# LED-Globe.net
KiCad netlist of a schematic drawn in EAGLE
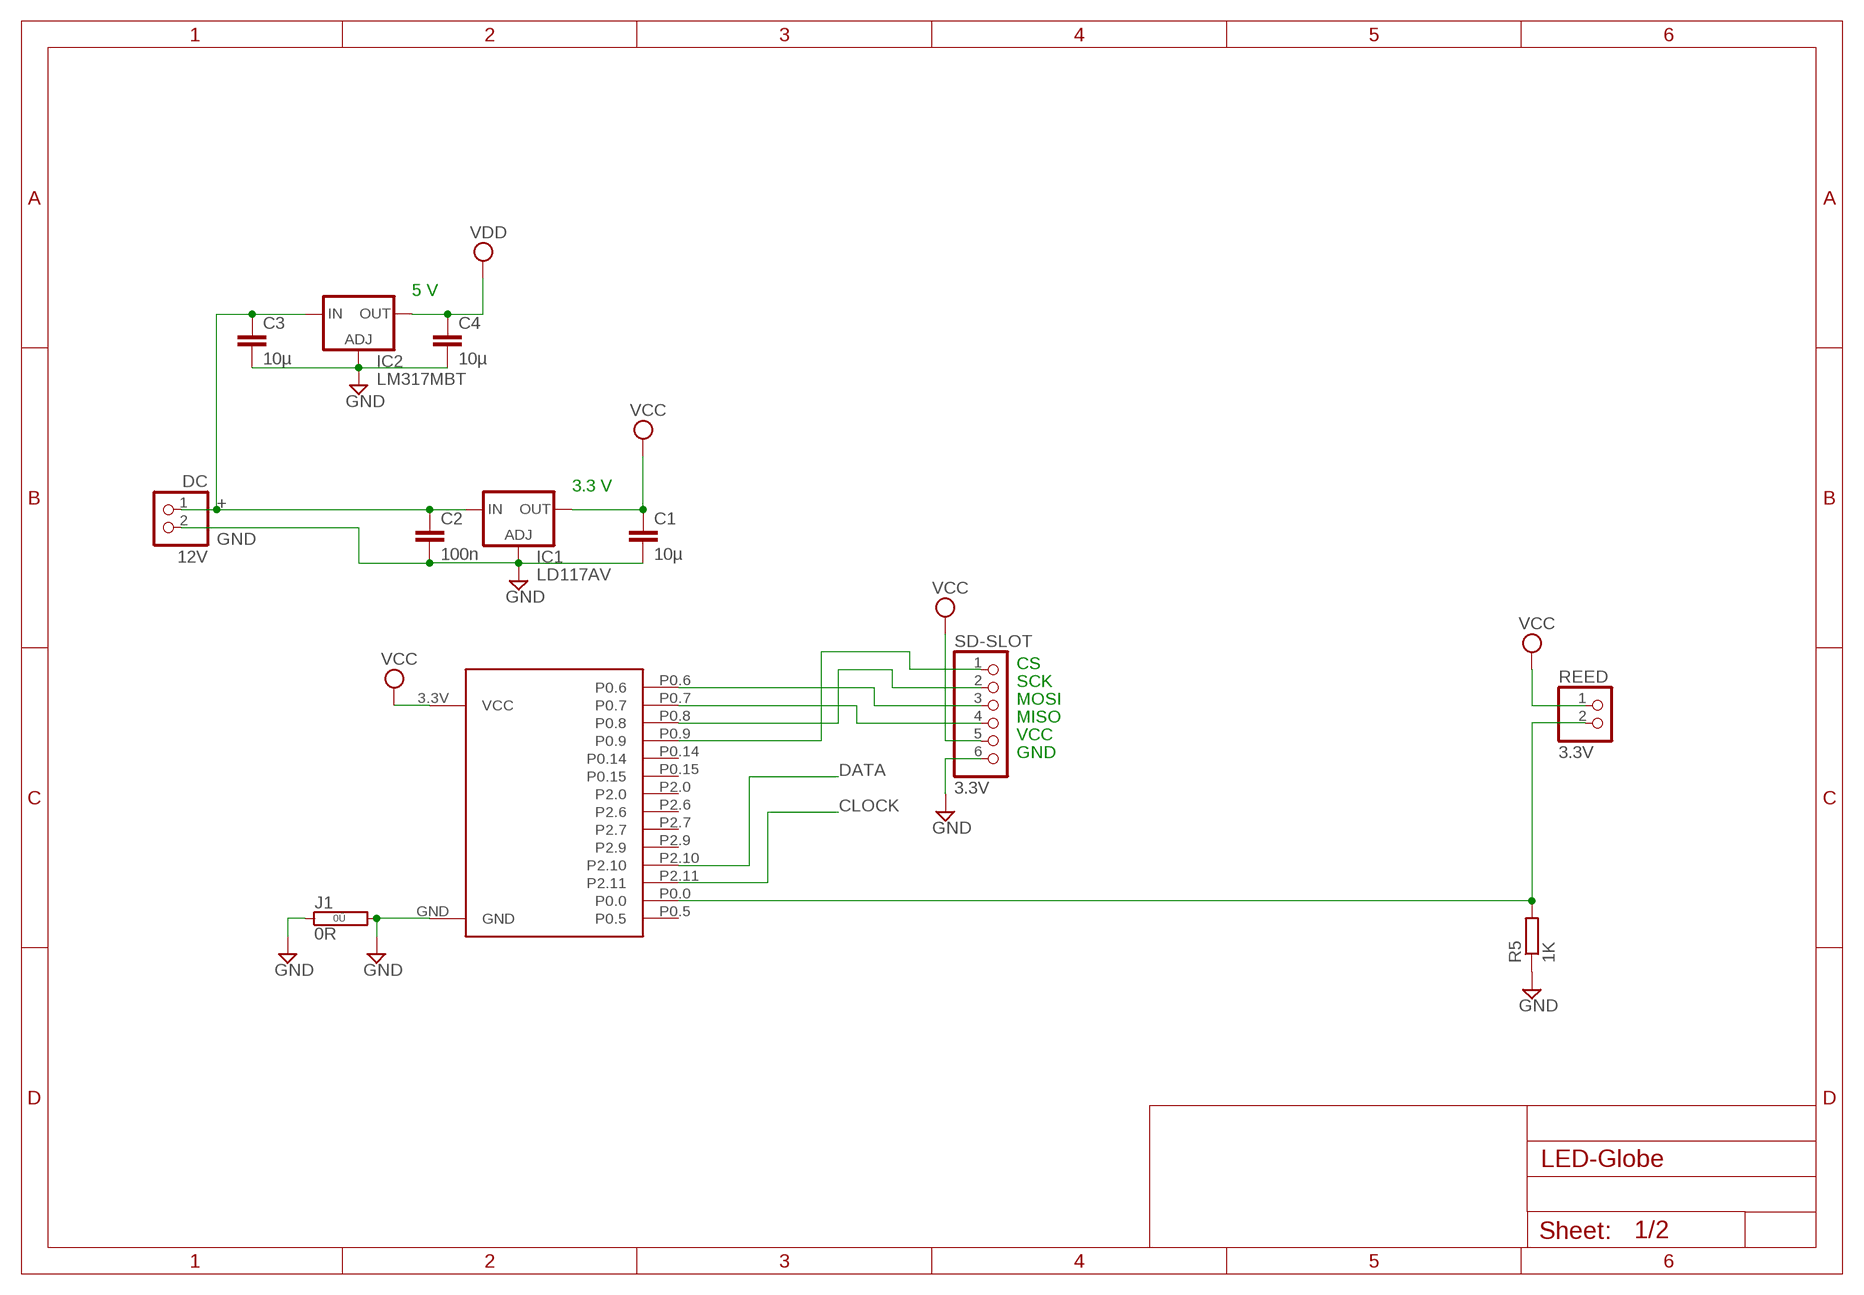
[diagram p0: schematic, sheet 1]
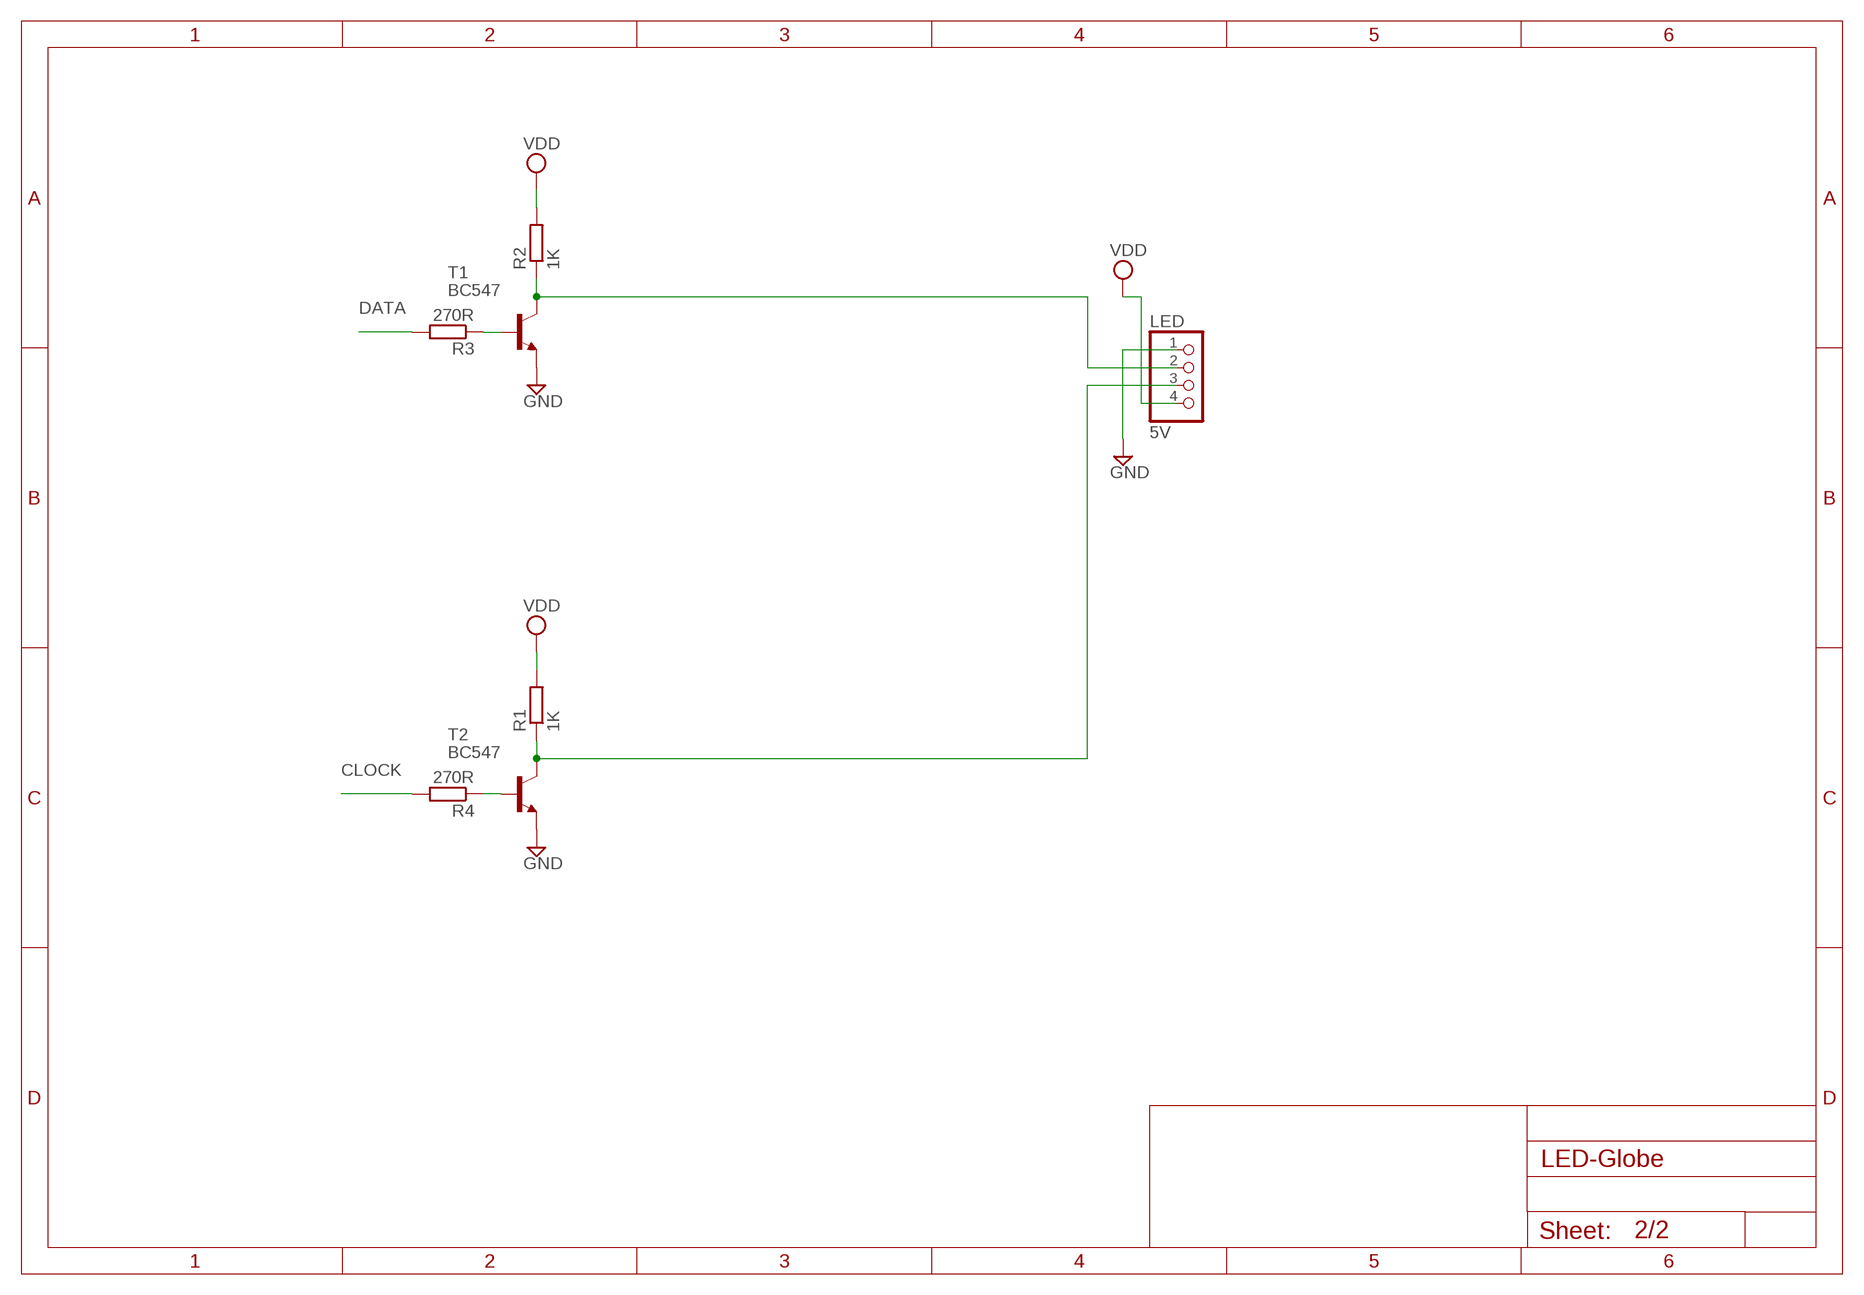
[diagram p1: schematic, sheet 2]

(export (version "E")
  (design (tool "Eeschema 10.0.6"))
  (components
    (comp (ref "C1")
      (value "10µ")
      (footprint "eagle-import:C025-024X044")
      (libsource (lib "eagle-import") (part "C-EU025-024X044"))
    )
    (comp (ref "C2")
      (value "100n")
      (footprint "eagle-import:C050-024X044")
      (libsource (lib "eagle-import") (part "C-EU050-024X044"))
    )
    (comp (ref "C3")
      (value "10µ")
      (footprint "eagle-import:C025-024X044")
      (libsource (lib "eagle-import") (part "C-EU025-024X044"))
    )
    (comp (ref "C4")
      (value "10µ")
      (footprint "eagle-import:C025-024X044")
      (libsource (lib "eagle-import") (part "C-EU025-024X044"))
    )
    (comp (ref "DC")
      (value "12V")
      (footprint "eagle-import:1X02")
      (libsource (lib "eagle-import") (part "PINHD-1X2"))
    )
    (comp (ref "IC1")
      (value "LD117AV")
      (footprint "eagle-import:TO220L1")
      (libsource (lib "eagle-import") (part "LD117A?V"))
    )
    (comp (ref "IC2")
      (value "LM317MBT")
      (footprint "eagle-import:TO220L1")
      (libsource (lib "eagle-import") (part "LM317?MBT"))
    )
    (comp (ref "J1")
      (value "0R")
      (footprint "eagle-import:0R_10")
      (libsource (lib "eagle-import") (part "0R"))
    )
    (comp (ref "R5")
      (value "1K")
      (footprint "eagle-import:0207_10")
      (libsource (lib "eagle-import") (part "R-EU_0207/10"))
    )
    (comp (ref "REED")
      (value "3.3V")
      (footprint "eagle-import:1X02")
      (libsource (lib "eagle-import") (part "PINHD-1X2"))
    )
    (comp (ref "SD-SLOT")
      (value "3.3V")
      (footprint "eagle-import:1X06")
      (libsource (lib "eagle-import") (part "PINHD-1X6"))
    )
    (comp (ref "XMC1")
      (value "XMC2GO")
      (footprint "eagle-import:XMC2GO")
      (libsource (lib "eagle-import") (part "XMC2GO"))
    )
    (comp (ref "LED")
      (value "5V")
      (footprint "eagle-import:1X04")
      (libsource (lib "eagle-import") (part "PINHD-1X4"))
    )
    (comp (ref "R1")
      (value "1K")
      (footprint "eagle-import:0207_10")
      (libsource (lib "eagle-import") (part "R-EU_0207/10"))
    )
    (comp (ref "R2")
      (value "1K")
      (footprint "eagle-import:0207_10")
      (libsource (lib "eagle-import") (part "R-EU_0207/10"))
    )
    (comp (ref "R3")
      (value "270R")
      (footprint "eagle-import:0207_10")
      (libsource (lib "eagle-import") (part "R-EU_0207/10"))
    )
    (comp (ref "R4")
      (value "270R")
      (footprint "eagle-import:0207_10")
      (libsource (lib "eagle-import") (part "R-EU_0207/10"))
    )
    (comp (ref "T1")
      (value "BC547")
      (footprint "eagle-import:TO92")
      (libsource (lib "eagle-import") (part "BC547"))
    )
    (comp (ref "T2")
      (value "BC547")
      (footprint "eagle-import:TO92")
      (libsource (lib "eagle-import") (part "BC547"))
    )
  )
  (nets
    (net (code "1") (name "+") (class "Default")
      (node (ref "C2") (pin "1") (pinfunction "1_1") (pintype "passive"))
      (node (ref "C3") (pin "1") (pinfunction "1_1") (pintype "passive"))
      (node (ref "DC") (pin "1") (pinfunction "1_1") (pintype "passive"))
      (node (ref "IC1") (pin "3") (pinfunction "IN_3") (pintype "input"))
      (node (ref "IC2") (pin "3") (pinfunction "IN_3") (pintype "input"))
    )
    (net (code "2") (name "CLOCK") (class "Default")
      (node (ref "R4") (pin "2") (pinfunction "2_2") (pintype "passive"))
      (node (ref "XMC1") (pin "P2.11") (pinfunction "P2.11_P2.11") (pintype "bidirectional"))
    )
    (net (code "3") (name "DATA") (class "Default")
      (node (ref "R3") (pin "2") (pinfunction "2_2") (pintype "passive"))
      (node (ref "XMC1") (pin "P2.10") (pinfunction "P2.10_P2.10") (pintype "bidirectional"))
    )
    (net (code "4") (name "GND") (class "Default")
      (node (ref "C1") (pin "2") (pinfunction "2_2") (pintype "passive"))
      (node (ref "C2") (pin "2") (pinfunction "2_2") (pintype "passive"))
      (node (ref "C3") (pin "2") (pinfunction "2_2") (pintype "passive"))
      (node (ref "C4") (pin "2") (pinfunction "2_2") (pintype "passive"))
      (node (ref "DC") (pin "2") (pinfunction "2_2") (pintype "passive"))
      (node (ref "IC1") (pin "1") (pinfunction "ADJ_1") (pintype "input"))
      (node (ref "IC2") (pin "1") (pinfunction "ADJ_1") (pintype "input"))
      (node (ref "J1") (pin "1") (pinfunction "1_1") (pintype "passive"))
      (node (ref "J1") (pin "2") (pinfunction "2_2") (pintype "passive"))
      (node (ref "LED") (pin "1") (pinfunction "1_1") (pintype "passive"))
      (node (ref "R5") (pin "1") (pinfunction "1_1") (pintype "passive"))
      (node (ref "SD-SLOT") (pin "6") (pinfunction "6_6") (pintype "passive"))
      (node (ref "T1") (pin "1") (pinfunction "E_1") (pintype "passive"))
      (node (ref "T2") (pin "1") (pinfunction "E_1") (pintype "passive"))
      (node (ref "XMC1") (pin "GND") (pinfunction "GND_GND") (pintype "power_in"))
    )
    (net (code "5") (name "Net-(R5-Pad2)") (class "Default")
      (node (ref "R5") (pin "2") (pinfunction "2_2") (pintype "passive"))
      (node (ref "REED") (pin "2") (pinfunction "2_2") (pintype "passive"))
      (node (ref "XMC1") (pin "P0.0") (pinfunction "P0.0_P0.0") (pintype "bidirectional"))
    )
    (net (code "6") (name "Net-(SD-SLOT-Pad1)") (class "Default")
      (node (ref "SD-SLOT") (pin "1") (pinfunction "1_1") (pintype "passive"))
      (node (ref "XMC1") (pin "P0.9") (pinfunction "P0.9_P0.9") (pintype "bidirectional"))
    )
    (net (code "7") (name "Net-(SD-SLOT-Pad2)") (class "Default")
      (node (ref "SD-SLOT") (pin "2") (pinfunction "2_2") (pintype "passive"))
      (node (ref "XMC1") (pin "P0.8") (pinfunction "P0.8_P0.8") (pintype "bidirectional"))
    )
    (net (code "8") (name "Net-(SD-SLOT-Pad3)") (class "Default")
      (node (ref "SD-SLOT") (pin "3") (pinfunction "3_3") (pintype "passive"))
      (node (ref "XMC1") (pin "P0.6") (pinfunction "P0.6_P0.6") (pintype "bidirectional"))
    )
    (net (code "9") (name "Net-(SD-SLOT-Pad4)") (class "Default")
      (node (ref "SD-SLOT") (pin "4") (pinfunction "4_4") (pintype "passive"))
      (node (ref "XMC1") (pin "P0.7") (pinfunction "P0.7_P0.7") (pintype "bidirectional"))
    )
    (net (code "10") (name "Net-(T1-B)") (class "Default")
      (node (ref "R3") (pin "1") (pinfunction "1_1") (pintype "passive"))
      (node (ref "T1") (pin "2") (pinfunction "B_2") (pintype "passive"))
    )
    (net (code "11") (name "Net-(T1-C)") (class "Default")
      (node (ref "LED") (pin "2") (pinfunction "2_2") (pintype "passive"))
      (node (ref "R2") (pin "1") (pinfunction "1_1") (pintype "passive"))
      (node (ref "T1") (pin "3") (pinfunction "C_3") (pintype "passive"))
    )
    (net (code "12") (name "Net-(T2-B)") (class "Default")
      (node (ref "R4") (pin "1") (pinfunction "1_1") (pintype "passive"))
      (node (ref "T2") (pin "2") (pinfunction "B_2") (pintype "passive"))
    )
    (net (code "13") (name "Net-(T2-C)") (class "Default")
      (node (ref "LED") (pin "3") (pinfunction "3_3") (pintype "passive"))
      (node (ref "R1") (pin "1") (pinfunction "1_1") (pintype "passive"))
      (node (ref "T2") (pin "3") (pinfunction "C_3") (pintype "passive"))
    )
    (net (code "14") (name "VCC") (class "Default")
      (node (ref "C1") (pin "1") (pinfunction "1_1") (pintype "passive"))
      (node (ref "IC1") (pin "2") (pinfunction "OUT_2") (pintype "passive"))
      (node (ref "REED") (pin "1") (pinfunction "1_1") (pintype "passive"))
      (node (ref "SD-SLOT") (pin "5") (pinfunction "5_5") (pintype "passive"))
      (node (ref "XMC1") (pin "3.3V") (pinfunction "VCC_3.3V") (pintype "power_in"))
    )
    (net (code "15") (name "VDD") (class "Default")
      (node (ref "C4") (pin "1") (pinfunction "1_1") (pintype "passive"))
      (node (ref "IC2") (pin "2") (pinfunction "OUT_2") (pintype "passive"))
      (node (ref "LED") (pin "4") (pinfunction "4_4") (pintype "passive"))
      (node (ref "R1") (pin "2") (pinfunction "2_2") (pintype "passive"))
      (node (ref "R2") (pin "2") (pinfunction "2_2") (pintype "passive"))
    )
    (net (code "16") (name "unconnected-(XMC1-PadP0.5)") (class "Default")
      (node (ref "XMC1") (pin "P0.5") (pinfunction "P0.5_P0.5") (pintype "bidirectional"))
    )
    (net (code "17") (name "unconnected-(XMC1-PadP0.14)") (class "Default")
      (node (ref "XMC1") (pin "P0.14") (pinfunction "P0.14_P0.14") (pintype "bidirectional"))
    )
    (net (code "18") (name "unconnected-(XMC1-PadP0.15)") (class "Default")
      (node (ref "XMC1") (pin "P0.15") (pinfunction "P0.15_P0.15") (pintype "bidirectional"))
    )
    (net (code "19") (name "unconnected-(XMC1-PadP2.0)") (class "Default")
      (node (ref "XMC1") (pin "P2.0") (pinfunction "P2.0_P2.0") (pintype "bidirectional"))
    )
    (net (code "20") (name "unconnected-(XMC1-PadP2.6)") (class "Default")
      (node (ref "XMC1") (pin "P2.6") (pinfunction "P2.6_P2.6") (pintype "bidirectional"))
    )
    (net (code "21") (name "unconnected-(XMC1-PadP2.7)") (class "Default")
      (node (ref "XMC1") (pin "P2.7") (pinfunction "P2.7_P2.7") (pintype "bidirectional"))
    )
    (net (code "22") (name "unconnected-(XMC1-PadP2.9)") (class "Default")
      (node (ref "XMC1") (pin "P2.9") (pinfunction "P2.9_P2.9") (pintype "bidirectional"))
    )
  )
)
